# Music.net
KiCad netlist of a schematic drawn in Altium Designer
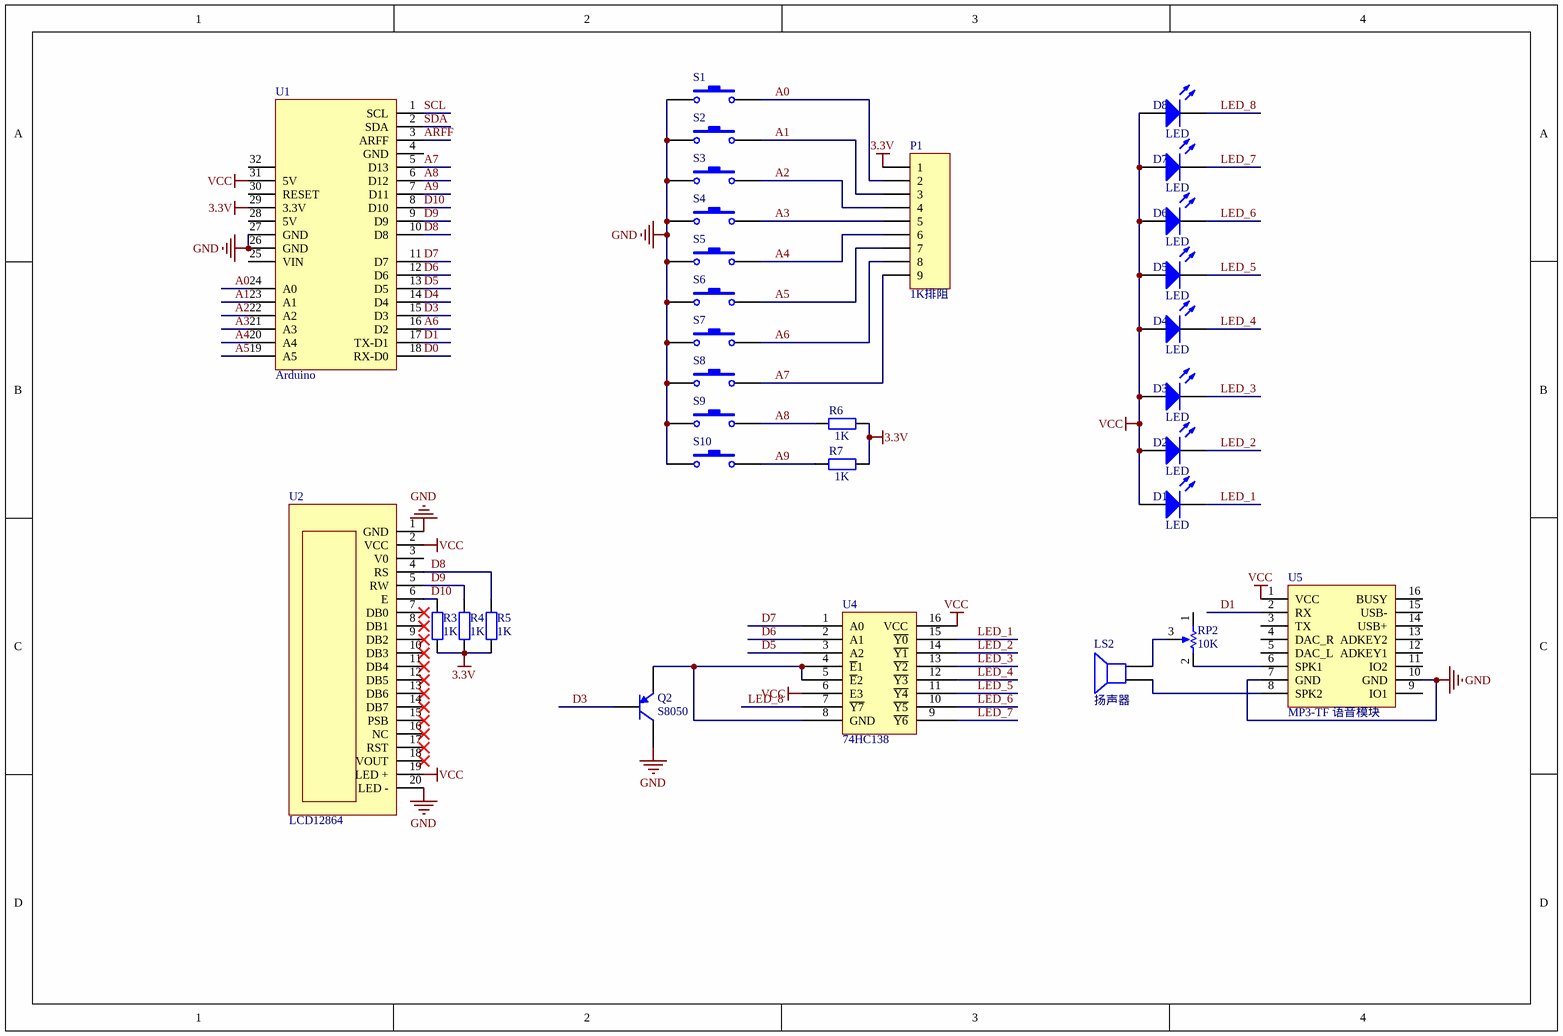
[diagram p0: Music.SchDoc]

(export (version "E")
  (design (tool "Eeschema 10.0.6"))
  (components
    (comp (ref "D1")
      (value "LED")
      (footprint "LED灯")
      (description "Typical INFRARED GaAs LED")
      (fields (field (name "PUBLISHER") "Altium Limited"))
      (libsource (lib "Miscellaneous Devices") (part "LED0"))
    )
    (comp (ref "D2")
      (value "LED")
      (footprint "LED灯")
      (description "Typical INFRARED GaAs LED")
      (fields (field (name "PUBLISHER") "Altium Limited"))
      (libsource (lib "Miscellaneous Devices") (part "LED0"))
    )
    (comp (ref "D3")
      (value "LED")
      (footprint "LED灯")
      (description "Typical INFRARED GaAs LED")
      (fields (field (name "PUBLISHER") "Altium Limited"))
      (libsource (lib "Miscellaneous Devices") (part "LED0"))
    )
    (comp (ref "D4")
      (value "LED")
      (footprint "LED灯")
      (description "Typical INFRARED GaAs LED")
      (fields (field (name "PUBLISHER") "Altium Limited"))
      (libsource (lib "Miscellaneous Devices") (part "LED0"))
    )
    (comp (ref "D5")
      (value "LED")
      (footprint "LED灯")
      (description "Typical INFRARED GaAs LED")
      (fields (field (name "PUBLISHER") "Altium Limited"))
      (libsource (lib "Miscellaneous Devices") (part "LED0"))
    )
    (comp (ref "D6")
      (value "LED")
      (footprint "LED灯")
      (description "Typical INFRARED GaAs LED")
      (fields (field (name "PUBLISHER") "Altium Limited"))
      (libsource (lib "Miscellaneous Devices") (part "LED0"))
    )
    (comp (ref "D7")
      (value "LED")
      (footprint "LED灯")
      (description "Typical INFRARED GaAs LED")
      (fields (field (name "PUBLISHER") "Altium Limited"))
      (libsource (lib "Miscellaneous Devices") (part "LED0"))
    )
    (comp (ref "D8")
      (value "LED")
      (footprint "LED灯")
      (description "Typical INFRARED GaAs LED")
      (fields (field (name "PUBLISHER") "Altium Limited"))
      (libsource (lib "Miscellaneous Devices") (part "LED0"))
    )
    (comp (ref "LS2")
      (value "扬声器")
      (footprint "PIN2")
      (description "Loudspeaker")
      (fields (field (name "PUBLISHER") "Altium Limited"))
      (libsource (lib "Miscellaneous Devices") (part "Speaker"))
    )
    (comp (ref "P1") (value "1K排阻") (footprint "9kong-公用") (libsource (lib "Schlib1") (part "9kong--排阻")))
    (comp (ref "Q2")
      (value "S8050")
      (footprint "三极管")
      (description "PNP General Purpose Amplifier")
      (fields (field (name "PUBLISHER") "Altium Limited"))
      (libsource (lib "Miscellaneous Devices") (part "2N3906"))
    )
    (comp (ref "R3")
      (value "1K")
      (footprint "AXIAL-0.4")
      (description "Resistor")
      (fields (field (name "PUBLISHER") "Altium Limited"))
      (libsource (lib "Miscellaneous Devices") (part "Res2"))
    )
    (comp (ref "R4")
      (value "1K")
      (footprint "AXIAL-0.4")
      (description "Resistor")
      (fields (field (name "PUBLISHER") "Altium Limited"))
      (libsource (lib "Miscellaneous Devices") (part "Res2"))
    )
    (comp (ref "R5")
      (value "1K")
      (footprint "AXIAL-0.4")
      (description "Resistor")
      (fields (field (name "PUBLISHER") "Altium Limited"))
      (libsource (lib "Miscellaneous Devices") (part "Res2"))
    )
    (comp (ref "R6")
      (value "1K")
      (footprint "AXIAL-0.4")
      (description "Resistor")
      (fields (field (name "PUBLISHER") "Altium Limited"))
      (libsource (lib "") (part "Res2_1"))
    )
    (comp (ref "R7")
      (value "1K")
      (footprint "AXIAL-0.4")
      (description "Resistor")
      (fields (field (name "PUBLISHER") "Altium Limited"))
      (libsource (lib "") (part "Res2_1"))
    )
    (comp (ref "RP2")
      (value "10K")
      (footprint "3kong-公用")
      (description "Potentiometer")
      (fields (field (name "PUBLISHER") "Altium Limited"))
      (libsource (lib "Miscellaneous Devices") (part "RPot"))
    )
    (comp (ref "S1")
      (value "~")
      (footprint "4kong-独立按键")
      (description "Switch")
      (fields (field (name "PUBLISHER") "Altium Limited"))
      (libsource (lib "Miscellaneous Devices") (part "SW-PB"))
    )
    (comp (ref "S2")
      (value "~")
      (footprint "4kong-独立按键")
      (description "Switch")
      (fields (field (name "PUBLISHER") "Altium Limited"))
      (libsource (lib "Miscellaneous Devices") (part "SW-PB"))
    )
    (comp (ref "S3")
      (value "~")
      (footprint "4kong-独立按键")
      (description "Switch")
      (fields (field (name "PUBLISHER") "Altium Limited"))
      (libsource (lib "Miscellaneous Devices") (part "SW-PB"))
    )
    (comp (ref "S4")
      (value "~")
      (footprint "4kong-独立按键")
      (description "Switch")
      (fields (field (name "PUBLISHER") "Altium Limited"))
      (libsource (lib "Miscellaneous Devices") (part "SW-PB"))
    )
    (comp (ref "S5")
      (value "~")
      (footprint "4kong-独立按键")
      (description "Switch")
      (fields (field (name "PUBLISHER") "Altium Limited"))
      (libsource (lib "Miscellaneous Devices") (part "SW-PB"))
    )
    (comp (ref "S6")
      (value "~")
      (footprint "4kong-独立按键")
      (description "Switch")
      (fields (field (name "PUBLISHER") "Altium Limited"))
      (libsource (lib "Miscellaneous Devices") (part "SW-PB"))
    )
    (comp (ref "S7")
      (value "~")
      (footprint "4kong-独立按键")
      (description "Switch")
      (fields (field (name "PUBLISHER") "Altium Limited"))
      (libsource (lib "Miscellaneous Devices") (part "SW-PB"))
    )
    (comp (ref "S8")
      (value "~")
      (footprint "4kong-独立按键")
      (description "Switch")
      (fields (field (name "PUBLISHER") "Altium Limited"))
      (libsource (lib "Miscellaneous Devices") (part "SW-PB"))
    )
    (comp (ref "S9")
      (value "~")
      (footprint "4kong-独立按键")
      (description "Switch")
      (fields (field (name "PUBLISHER") "Altium Limited"))
      (libsource (lib "Miscellaneous Devices") (part "SW-PB"))
    )
    (comp (ref "S10")
      (value "~")
      (footprint "4kong-独立按键")
      (description "Switch")
      (fields (field (name "PUBLISHER") "Altium Limited"))
      (libsource (lib "Miscellaneous Devices") (part "SW-PB"))
    )
    (comp (ref "U1") (value "Arduino") (footprint "Arduino单片机") (libsource (lib "Schlib1") (part "Arduino")))
    (comp (ref "U2") (value "LCD12864") (footprint "LCD12864") (libsource (lib "Schlib1") (part "LCD12864")))
    (comp (ref "U4") (value "74HC138") (footprint "8+8双排16孔") (libsource (lib "Schlib1") (part "74HC138")))
    (comp (ref "U5")
      (value "MP3-TF 语音模块")
      (footprint "MP3-TF 语音模块")
      (libsource (lib "Schlib1") (part "MP3-TF 语音模块"))
    )
  )
  (nets
    (net (code "1") (name "/A0") (class "Default")
      (node (ref "P1") (pin "2") (pinfunction "2_2") (pintype "passive"))
      (node (ref "S1") (pin "2") (pinfunction "2_2") (pintype "passive"))
      (node (ref "U1") (pin "24") (pinfunction "A0_24") (pintype "passive"))
    )
    (net (code "2") (name "/A1") (class "Default")
      (node (ref "P1") (pin "3") (pinfunction "3_3") (pintype "passive"))
      (node (ref "S2") (pin "2") (pinfunction "2_2") (pintype "passive"))
      (node (ref "U1") (pin "23") (pinfunction "A1_23") (pintype "passive"))
    )
    (net (code "3") (name "/A2") (class "Default")
      (node (ref "P1") (pin "4") (pinfunction "4_4") (pintype "passive"))
      (node (ref "S3") (pin "2") (pinfunction "2_2") (pintype "passive"))
      (node (ref "U1") (pin "22") (pinfunction "A2_22") (pintype "passive"))
    )
    (net (code "4") (name "/A3") (class "Default")
      (node (ref "P1") (pin "5") (pinfunction "5_5") (pintype "passive"))
      (node (ref "S4") (pin "2") (pinfunction "2_2") (pintype "passive"))
      (node (ref "U1") (pin "21") (pinfunction "A3_21") (pintype "passive"))
    )
    (net (code "5") (name "/A4") (class "Default")
      (node (ref "P1") (pin "6") (pinfunction "6_6") (pintype "passive"))
      (node (ref "S5") (pin "2") (pinfunction "2_2") (pintype "passive"))
      (node (ref "U1") (pin "20") (pinfunction "A4_20") (pintype "passive"))
    )
    (net (code "6") (name "/A5") (class "Default")
      (node (ref "P1") (pin "7") (pinfunction "7_7") (pintype "passive"))
      (node (ref "S6") (pin "2") (pinfunction "2_2") (pintype "passive"))
      (node (ref "U1") (pin "19") (pinfunction "A5_19") (pintype "passive"))
    )
    (net (code "7") (name "/A6") (class "Default")
      (node (ref "P1") (pin "8") (pinfunction "8_8") (pintype "passive"))
      (node (ref "S7") (pin "2") (pinfunction "2_2") (pintype "passive"))
      (node (ref "U1") (pin "16") (pinfunction "D2_16") (pintype "passive"))
    )
    (net (code "8") (name "/A7") (class "Default")
      (node (ref "P1") (pin "9") (pinfunction "9_9") (pintype "passive"))
      (node (ref "S8") (pin "2") (pinfunction "2_2") (pintype "passive"))
      (node (ref "U1") (pin "5") (pinfunction "D13_5") (pintype "passive"))
    )
    (net (code "9") (name "/A8") (class "Default")
      (node (ref "R6") (pin "1") (pinfunction "1_1") (pintype "passive"))
      (node (ref "S9") (pin "2") (pinfunction "2_2") (pintype "passive"))
      (node (ref "U1") (pin "6") (pinfunction "D12_6") (pintype "passive"))
    )
    (net (code "10") (name "/A9") (class "Default")
      (node (ref "R7") (pin "1") (pinfunction "1_1") (pintype "passive"))
      (node (ref "S10") (pin "2") (pinfunction "2_2") (pintype "passive"))
      (node (ref "U1") (pin "7") (pinfunction "D11_7") (pintype "passive"))
    )
    (net (code "11") (name "/ARFF") (class "Default")
      (node (ref "U1") (pin "3") (pinfunction "ARFF_3") (pintype "passive"))
    )
    (net (code "12") (name "/D0") (class "Default")
      (node (ref "U1") (pin "18") (pinfunction "RX-D0_18") (pintype "passive"))
    )
    (net (code "13") (name "/D1") (class "Default")
      (node (ref "U1") (pin "17") (pinfunction "TX-D1_17") (pintype "passive"))
      (node (ref "U5") (pin "2") (pinfunction "RX_2") (pintype "passive"))
    )
    (net (code "14") (name "/D3") (class "Default")
      (node (ref "Q2") (pin "2") (pinfunction "B_2") (pintype "passive"))
      (node (ref "U1") (pin "15") (pinfunction "D3_15") (pintype "passive"))
    )
    (net (code "15") (name "/D4") (class "Default")
      (node (ref "U1") (pin "14") (pinfunction "D4_14") (pintype "passive"))
    )
    (net (code "16") (name "/D5") (class "Default")
      (node (ref "U1") (pin "13") (pinfunction "D5_13") (pintype "passive"))
      (node (ref "U4") (pin "3") (pinfunction "A2_3") (pintype "power_in"))
    )
    (net (code "17") (name "/D6") (class "Default")
      (node (ref "U1") (pin "12") (pinfunction "D6_12") (pintype "passive"))
      (node (ref "U4") (pin "2") (pinfunction "A1_2") (pintype "power_in"))
    )
    (net (code "18") (name "/D7") (class "Default")
      (node (ref "U1") (pin "11") (pinfunction "D7_11") (pintype "passive"))
      (node (ref "U4") (pin "1") (pinfunction "A0_1") (pintype "power_in"))
    )
    (net (code "19") (name "/D8") (class "Default")
      (node (ref "R5") (pin "2") (pinfunction "2_2") (pintype "passive"))
      (node (ref "U1") (pin "10") (pinfunction "D8_10") (pintype "passive"))
      (node (ref "U2") (pin "4") (pinfunction "RS_4") (pintype "passive"))
    )
    (net (code "20") (name "/D9") (class "Default")
      (node (ref "R4") (pin "2") (pinfunction "2_2") (pintype "passive"))
      (node (ref "U1") (pin "9") (pinfunction "D9_9") (pintype "passive"))
      (node (ref "U2") (pin "5") (pinfunction "RW_5") (pintype "passive"))
    )
    (net (code "21") (name "/D10") (class "Default")
      (node (ref "R3") (pin "2") (pinfunction "2_2") (pintype "passive"))
      (node (ref "U1") (pin "8") (pinfunction "D10_8") (pintype "passive"))
      (node (ref "U2") (pin "6") (pinfunction "E_6") (pintype "passive"))
    )
    (net (code "22") (name "/LED_1") (class "Default")
      (node (ref "D1") (pin "2") (pinfunction "K_2") (pintype "passive"))
      (node (ref "U4") (pin "15") (pinfunction "~{Y0}_15") (pintype "power_in"))
    )
    (net (code "23") (name "/LED_2") (class "Default")
      (node (ref "D2") (pin "2") (pinfunction "K_2") (pintype "passive"))
      (node (ref "U4") (pin "14") (pinfunction "~{Y1}_14") (pintype "power_in"))
    )
    (net (code "24") (name "/LED_3") (class "Default")
      (node (ref "D3") (pin "2") (pinfunction "K_2") (pintype "passive"))
      (node (ref "U4") (pin "13") (pinfunction "~{Y2}_13") (pintype "power_in"))
    )
    (net (code "25") (name "/LED_4") (class "Default")
      (node (ref "D4") (pin "2") (pinfunction "K_2") (pintype "passive"))
      (node (ref "U4") (pin "12") (pinfunction "~{Y3}_12") (pintype "power_in"))
    )
    (net (code "26") (name "/LED_5") (class "Default")
      (node (ref "D5") (pin "2") (pinfunction "K_2") (pintype "passive"))
      (node (ref "U4") (pin "11") (pinfunction "~{Y4}_11") (pintype "power_in"))
    )
    (net (code "27") (name "/LED_6") (class "Default")
      (node (ref "D6") (pin "2") (pinfunction "K_2") (pintype "passive"))
      (node (ref "U4") (pin "10") (pinfunction "~{Y5}_10") (pintype "power_in"))
    )
    (net (code "28") (name "/LED_7") (class "Default")
      (node (ref "D7") (pin "2") (pinfunction "K_2") (pintype "passive"))
      (node (ref "U4") (pin "9") (pinfunction "~{Y6}_9") (pintype "power_in"))
    )
    (net (code "29") (name "/LED_8") (class "Default")
      (node (ref "D8") (pin "2") (pinfunction "K_2") (pintype "passive"))
      (node (ref "U4") (pin "7") (pinfunction "~{Y7}_7") (pintype "power_in"))
    )
    (net (code "30") (name "/SCL") (class "Default")
      (node (ref "U1") (pin "1") (pinfunction "SCL_1") (pintype "passive"))
    )
    (net (code "31") (name "/SDA") (class "Default")
      (node (ref "U1") (pin "2") (pinfunction "SDA_2") (pintype "passive"))
    )
    (net (code "32") (name "3.3V") (class "Default")
      (node (ref "P1") (pin "1") (pinfunction "1_1") (pintype "passive"))
      (node (ref "R3") (pin "1") (pinfunction "1_1") (pintype "passive"))
      (node (ref "R4") (pin "1") (pinfunction "1_1") (pintype "passive"))
      (node (ref "R5") (pin "1") (pinfunction "1_1") (pintype "passive"))
      (node (ref "R6") (pin "2") (pinfunction "2_2") (pintype "passive"))
      (node (ref "R7") (pin "2") (pinfunction "2_2") (pintype "passive"))
      (node (ref "U1") (pin "29") (pinfunction "3.3V_29") (pintype "passive"))
    )
    (net (code "33") (name "GND") (class "Default")
      (node (ref "Q2") (pin "3") (pinfunction "C_3") (pintype "passive"))
      (node (ref "S1") (pin "1") (pinfunction "1_1") (pintype "passive"))
      (node (ref "S10") (pin "1") (pinfunction "1_1") (pintype "passive"))
      (node (ref "S2") (pin "1") (pinfunction "1_1") (pintype "passive"))
      (node (ref "S3") (pin "1") (pinfunction "1_1") (pintype "passive"))
      (node (ref "S4") (pin "1") (pinfunction "1_1") (pintype "passive"))
      (node (ref "S5") (pin "1") (pinfunction "1_1") (pintype "passive"))
      (node (ref "S6") (pin "1") (pinfunction "1_1") (pintype "passive"))
      (node (ref "S7") (pin "1") (pinfunction "1_1") (pintype "passive"))
      (node (ref "S8") (pin "1") (pinfunction "1_1") (pintype "passive"))
      (node (ref "S9") (pin "1") (pinfunction "1_1") (pintype "passive"))
      (node (ref "U1") (pin "26") (pinfunction "GND_26") (pintype "passive"))
      (node (ref "U1") (pin "27") (pinfunction "GND_27") (pintype "passive"))
      (node (ref "U2") (pin "1") (pinfunction "GND_1") (pintype "passive"))
      (node (ref "U2") (pin "20") (pinfunction "LED_-_20") (pintype "passive"))
      (node (ref "U5") (pin "10") (pinfunction "GND_10") (pintype "passive"))
      (node (ref "U5") (pin "7") (pinfunction "GND_7") (pintype "passive"))
    )
    (net (code "34") (name "Net-(Q2-E)") (class "Default")
      (node (ref "Q2") (pin "1") (pinfunction "E_1") (pintype "passive"))
      (node (ref "U4") (pin "4") (pinfunction "~{E}1_4") (pintype "power_in"))
      (node (ref "U4") (pin "5") (pinfunction "~{E}2_5") (pintype "power_in"))
      (node (ref "U4") (pin "8") (pinfunction "GND_8") (pintype "power_in"))
    )
    (net (code "35") (name "Net-(RP2-BOT)") (class "Default")
      (node (ref "RP2") (pin "2") (pinfunction "BOT_2") (pintype "passive"))
      (node (ref "U5") (pin "6") (pinfunction "SPK1_6") (pintype "passive"))
    )
    (net (code "36") (name "Net-(RP2-TAP)") (class "Default")
      (node (ref "LS2") (pin "2") (pinfunction "2_2") (pintype "passive"))
      (node (ref "RP2") (pin "3") (pinfunction "TAP_3") (pintype "passive"))
    )
    (net (code "37") (name "Net-(U5-SPK2)") (class "Default")
      (node (ref "LS2") (pin "1") (pinfunction "1_1") (pintype "passive"))
      (node (ref "U5") (pin "8") (pinfunction "SPK2_8") (pintype "passive"))
    )
    (net (code "38") (name "VCC") (class "Default")
      (node (ref "D1") (pin "1") (pinfunction "A_1") (pintype "passive"))
      (node (ref "D2") (pin "1") (pinfunction "A_1") (pintype "passive"))
      (node (ref "D3") (pin "1") (pinfunction "A_1") (pintype "passive"))
      (node (ref "D4") (pin "1") (pinfunction "A_1") (pintype "passive"))
      (node (ref "D5") (pin "1") (pinfunction "A_1") (pintype "passive"))
      (node (ref "D6") (pin "1") (pinfunction "A_1") (pintype "passive"))
      (node (ref "D7") (pin "1") (pinfunction "A_1") (pintype "passive"))
      (node (ref "D8") (pin "1") (pinfunction "A_1") (pintype "passive"))
      (node (ref "U1") (pin "31") (pinfunction "5V_31") (pintype "passive"))
      (node (ref "U2") (pin "19") (pinfunction "LED_+_19") (pintype "passive"))
      (node (ref "U2") (pin "2") (pinfunction "VCC_2") (pintype "passive"))
      (node (ref "U4") (pin "16") (pinfunction "VCC_16") (pintype "power_in"))
      (node (ref "U4") (pin "6") (pinfunction "E3_6") (pintype "power_in"))
      (node (ref "U5") (pin "1") (pinfunction "VCC_1") (pintype "passive"))
    )
    (net (code "39") (name "unconnected-(RP2-TOP-Pad1)") (class "Default")
      (node (ref "RP2") (pin "1") (pinfunction "TOP_1") (pintype "passive"))
    )
    (net (code "40") (name "unconnected-(U1-5V-Pad28)") (class "Default")
      (node (ref "U1") (pin "28") (pinfunction "5V_28") (pintype "passive"))
    )
    (net (code "41") (name "unconnected-(U1-GND-Pad4)") (class "Default")
      (node (ref "U1") (pin "4") (pinfunction "GND_4") (pintype "passive"))
    )
    (net (code "42") (name "unconnected-(U1-Pad32)") (class "Default")
      (node (ref "U1") (pin "32") (pinfunction "32_32") (pintype "passive"))
    )
    (net (code "43") (name "unconnected-(U1-RESET-Pad30)") (class "Default")
      (node (ref "U1") (pin "30") (pinfunction "RESET_30") (pintype "passive"))
    )
    (net (code "44") (name "unconnected-(U1-VIN-Pad25)") (class "Default")
      (node (ref "U1") (pin "25") (pinfunction "VIN_25") (pintype "passive"))
    )
    (net (code "45") (name "unconnected-(U2-DB0-Pad7)") (class "Default")
      (node (ref "U2") (pin "7") (pinfunction "DB0_7") (pintype "passive+no_connect"))
    )
    (net (code "46") (name "unconnected-(U2-DB1-Pad8)") (class "Default")
      (node (ref "U2") (pin "8") (pinfunction "DB1_8") (pintype "passive+no_connect"))
    )
    (net (code "47") (name "unconnected-(U2-DB2-Pad9)") (class "Default")
      (node (ref "U2") (pin "9") (pinfunction "DB2_9") (pintype "passive+no_connect"))
    )
    (net (code "48") (name "unconnected-(U2-DB3-Pad10)") (class "Default")
      (node (ref "U2") (pin "10") (pinfunction "DB3_10") (pintype "passive+no_connect"))
    )
    (net (code "49") (name "unconnected-(U2-DB4-Pad11)") (class "Default")
      (node (ref "U2") (pin "11") (pinfunction "DB4_11") (pintype "passive+no_connect"))
    )
    (net (code "50") (name "unconnected-(U2-DB5-Pad12)") (class "Default")
      (node (ref "U2") (pin "12") (pinfunction "DB5_12") (pintype "passive+no_connect"))
    )
    (net (code "51") (name "unconnected-(U2-DB6-Pad13)") (class "Default")
      (node (ref "U2") (pin "13") (pinfunction "DB6_13") (pintype "passive+no_connect"))
    )
    (net (code "52") (name "unconnected-(U2-DB7-Pad14)") (class "Default")
      (node (ref "U2") (pin "14") (pinfunction "DB7_14") (pintype "passive+no_connect"))
    )
    (net (code "53") (name "unconnected-(U2-NC-Pad16)") (class "Default")
      (node (ref "U2") (pin "16") (pinfunction "NC_16") (pintype "passive+no_connect"))
    )
    (net (code "54") (name "unconnected-(U2-PSB-Pad15)") (class "Default")
      (node (ref "U2") (pin "15") (pinfunction "PSB_15") (pintype "passive+no_connect"))
    )
    (net (code "55") (name "unconnected-(U2-RST-Pad17)") (class "Default")
      (node (ref "U2") (pin "17") (pinfunction "RST_17") (pintype "passive+no_connect"))
    )
    (net (code "56") (name "unconnected-(U2-V0-Pad3)") (class "Default")
      (node (ref "U2") (pin "3") (pinfunction "V0_3") (pintype "passive"))
    )
    (net (code "57") (name "unconnected-(U2-VOUT-Pad18)") (class "Default")
      (node (ref "U2") (pin "18") (pinfunction "VOUT_18") (pintype "passive+no_connect"))
    )
    (net (code "58") (name "unconnected-(U5-ADKEY1-Pad12)") (class "Default")
      (node (ref "U5") (pin "12") (pinfunction "ADKEY1_12") (pintype "passive"))
    )
    (net (code "59") (name "unconnected-(U5-ADKEY2-Pad13)") (class "Default")
      (node (ref "U5") (pin "13") (pinfunction "ADKEY2_13") (pintype "passive"))
    )
    (net (code "60") (name "unconnected-(U5-BUSY-Pad16)") (class "Default")
      (node (ref "U5") (pin "16") (pinfunction "BUSY_16") (pintype "passive"))
    )
    (net (code "61") (name "unconnected-(U5-DAC_L-Pad5)") (class "Default")
      (node (ref "U5") (pin "5") (pinfunction "DAC_L_5") (pintype "passive"))
    )
    (net (code "62") (name "unconnected-(U5-DAC_R-Pad4)") (class "Default")
      (node (ref "U5") (pin "4") (pinfunction "DAC_R_4") (pintype "passive"))
    )
    (net (code "63") (name "unconnected-(U5-IO1-Pad9)") (class "Default")
      (node (ref "U5") (pin "9") (pinfunction "IO1_9") (pintype "passive"))
    )
    (net (code "64") (name "unconnected-(U5-IO2-Pad11)") (class "Default")
      (node (ref "U5") (pin "11") (pinfunction "IO2_11") (pintype "passive"))
    )
    (net (code "65") (name "unconnected-(U5-TX-Pad3)") (class "Default")
      (node (ref "U5") (pin "3") (pinfunction "TX_3") (pintype "passive"))
    )
    (net (code "66") (name "unconnected-(U5-USB+-Pad14)") (class "Default")
      (node (ref "U5") (pin "14") (pinfunction "USB+_14") (pintype "passive"))
    )
    (net (code "67") (name "unconnected-(U5-USB--Pad15)") (class "Default")
      (node (ref "U5") (pin "15") (pinfunction "USB-_15") (pintype "passive"))
    )
  )
)
